# MiP_D1_mini_Pack_v1.net
KiCad netlist of a schematic drawn in EAGLE
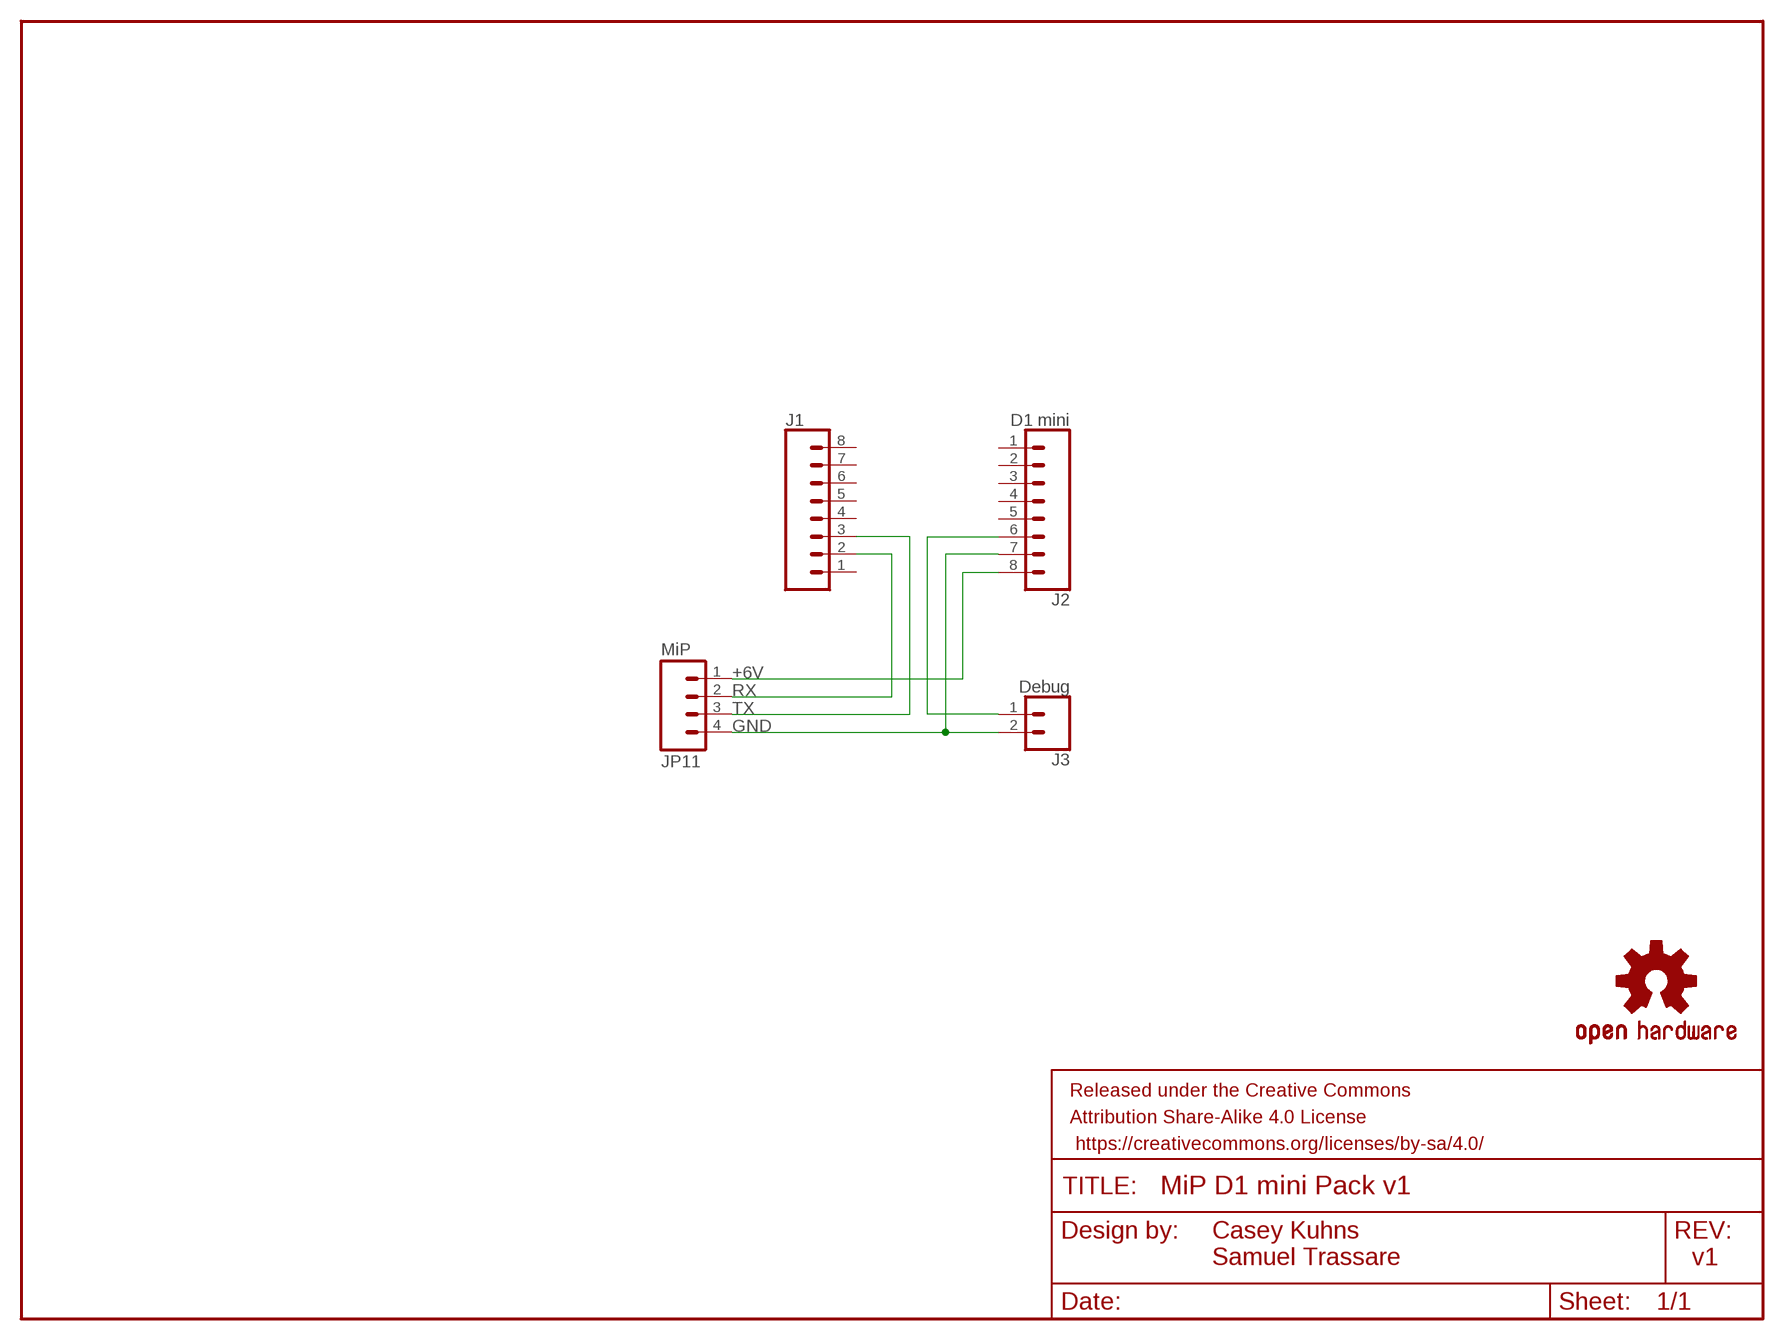
[diagram p0: schematic, sheet 1]

(export (version "E")
  (design (tool "Eeschema 10.0.6"))
  (components
    (comp (ref "FRAME1")
      (value "FRAME-LETTER")
      (footprint "eagle-import:CREATIVE_COMMONS")
      (libsource (lib "eagle-import") (part "FRAME-LETTER"))
    )
    (comp (ref "J1")
      (value "CONN_08\"")
      (footprint "eagle-import:1X08")
      (libsource (lib "eagle-import") (part "CONN_08{dblquote}"))
    )
    (comp (ref "J2")
      (value "D1 mini")
      (footprint "eagle-import:1X08")
      (libsource (lib "eagle-import") (part "CONN_08{dblquote}"))
    )
    (comp (ref "J3")
      (value "Debug")
      (footprint "eagle-import:1X02_RA_PTH_FEMALE")
      (libsource (lib "eagle-import") (part "CONN_02PTH_RA_FEMALE"))
    )
    (comp (ref "JP11")
      (value "MiP")
      (footprint "eagle-import:1X04-1.5MM_JST")
      (libsource (lib "eagle-import") (part "M04JST"))
    )
    (comp (ref "LOGO2")
      (value "OSHW-LOGOS")
      (footprint "eagle-import:OSHW-LOGO-S")
      (libsource (lib "eagle-import") (part "OSHW-LOGOS"))
    )
  )
  (nets
    (net (code "1") (name "/+6V") (class "Default")
      (node (ref "J2") (pin "8") (pinfunction "8_8") (pintype "passive"))
      (node (ref "JP11") (pin "1") (pinfunction "1_1") (pintype "passive"))
    )
    (net (code "2") (name "/GND") (class "Default")
      (node (ref "J2") (pin "7") (pinfunction "7_7") (pintype "passive"))
      (node (ref "J3") (pin "2") (pinfunction "2_2") (pintype "passive"))
      (node (ref "JP11") (pin "4") (pinfunction "4_4") (pintype "passive"))
    )
    (net (code "3") (name "/RX") (class "Default")
      (node (ref "J1") (pin "2") (pinfunction "2_2") (pintype "passive"))
      (node (ref "JP11") (pin "2") (pinfunction "2_2") (pintype "passive"))
    )
    (net (code "4") (name "/TX") (class "Default")
      (node (ref "J1") (pin "3") (pinfunction "3_3") (pintype "passive"))
      (node (ref "JP11") (pin "3") (pinfunction "3_3") (pintype "passive"))
    )
    (net (code "5") (name "Net-(J2-Pad6)") (class "Default")
      (node (ref "J2") (pin "6") (pinfunction "6_6") (pintype "passive"))
      (node (ref "J3") (pin "1") (pinfunction "1_1") (pintype "passive"))
    )
    (net (code "6") (name "unconnected-(J1-Pad1)") (class "Default")
      (node (ref "J1") (pin "1") (pinfunction "1_1") (pintype "passive"))
    )
    (net (code "7") (name "unconnected-(J1-Pad4)") (class "Default")
      (node (ref "J1") (pin "4") (pinfunction "4_4") (pintype "passive"))
    )
    (net (code "8") (name "unconnected-(J1-Pad5)") (class "Default")
      (node (ref "J1") (pin "5") (pinfunction "5_5") (pintype "passive"))
    )
    (net (code "9") (name "unconnected-(J1-Pad6)") (class "Default")
      (node (ref "J1") (pin "6") (pinfunction "6_6") (pintype "passive"))
    )
    (net (code "10") (name "unconnected-(J1-Pad7)") (class "Default")
      (node (ref "J1") (pin "7") (pinfunction "7_7") (pintype "passive"))
    )
    (net (code "11") (name "unconnected-(J1-Pad8)") (class "Default")
      (node (ref "J1") (pin "8") (pinfunction "8_8") (pintype "passive"))
    )
    (net (code "12") (name "unconnected-(J2-Pad1)") (class "Default")
      (node (ref "J2") (pin "1") (pinfunction "1_1") (pintype "passive"))
    )
    (net (code "13") (name "unconnected-(J2-Pad2)") (class "Default")
      (node (ref "J2") (pin "2") (pinfunction "2_2") (pintype "passive"))
    )
    (net (code "14") (name "unconnected-(J2-Pad3)") (class "Default")
      (node (ref "J2") (pin "3") (pinfunction "3_3") (pintype "passive"))
    )
    (net (code "15") (name "unconnected-(J2-Pad4)") (class "Default")
      (node (ref "J2") (pin "4") (pinfunction "4_4") (pintype "passive"))
    )
    (net (code "16") (name "unconnected-(J2-Pad5)") (class "Default")
      (node (ref "J2") (pin "5") (pinfunction "5_5") (pintype "passive"))
    )
  )
)
